# ArduOSD_Simple.net
KiCad netlist of a schematic drawn in EAGLE
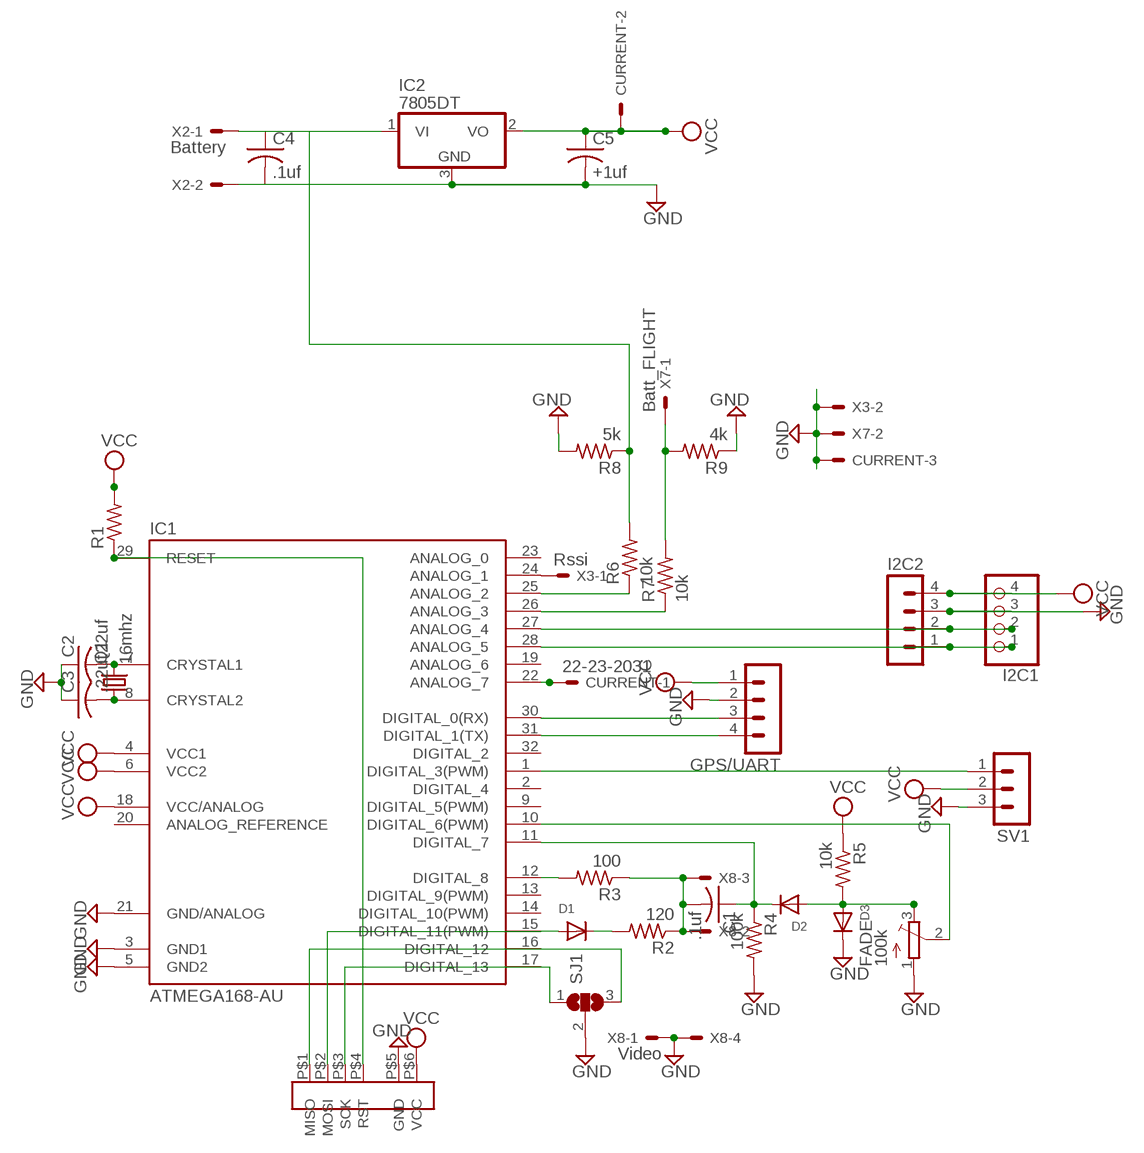
[diagram p0: schematic, sheet 1]

(export (version "E")
  (design (tool "Eeschema 10.0.6"))
  (components
    (comp (ref "C1")
      (value ".1uf")
      (footprint "eagle-import:C0805K")
      (libsource (lib "eagle-import") (part "C-USC0805K"))
    )
    (comp (ref "C2")
      (value ".22uf")
      (footprint "eagle-import:C0805K")
      (libsource (lib "eagle-import") (part "C-USC0805K"))
    )
    (comp (ref "C3")
      (value ".22uf")
      (footprint "eagle-import:C0805K")
      (libsource (lib "eagle-import") (part "C-USC0805K"))
    )
    (comp (ref "C4")
      (value ".1uf")
      (footprint "eagle-import:C0805K")
      (libsource (lib "eagle-import") (part "C-USC0805K"))
    )
    (comp (ref "C5")
      (value "+1uf")
      (footprint "eagle-import:C0805K")
      (libsource (lib "eagle-import") (part "C-USC0805K"))
    )
    (comp (ref "CURRENT")
      (value "22-23-2031")
      (footprint "eagle-import:22-23-2031")
      (fields (field (name "MF") "MOLEX"))
      (libsource (lib "eagle-import") (part "22-23-2031"))
    )
    (comp (ref "D1")
      (value "DIODESOT23_WAVE")
      (footprint "eagle-import:SOT23-W")
      (libsource (lib "eagle-import") (part "DIODESOT23_WAVE"))
    )
    (comp (ref "D2")
      (value "DIODESOT23_WAVE")
      (footprint "eagle-import:SOT23-W")
      (libsource (lib "eagle-import") (part "DIODESOT23_WAVE"))
    )
    (comp (ref "D3")
      (value "DIODESOT23_WAVE")
      (footprint "eagle-import:SOT23-W")
      (libsource (lib "eagle-import") (part "DIODESOT23_WAVE"))
    )
    (comp (ref "FADE")
      (value "100k")
      (footprint "eagle-import:TC33X")
      (libsource (lib "eagle-import") (part "TRIMPOTTC33X"))
    )
    (comp (ref "GPS/UART")
      (value "MA04-1")
      (footprint "eagle-import:MA04-1")
      (libsource (lib "eagle-import") (part "MA04-1"))
    )
    (comp (ref "I2C1")
      (value "PINHD-1X4")
      (footprint "eagle-import:1X04")
      (libsource (lib "eagle-import") (part "PINHD-1X4"))
    )
    (comp (ref "I2C2")
      (value "MA04-1")
      (footprint "eagle-import:MA04-1")
      (libsource (lib "eagle-import") (part "MA04-1"))
    )
    (comp (ref "IC1")
      (value "ATMEGA168-AU")
      (footprint "eagle-import:TQFP32-08")
      (libsource (lib "eagle-import") (part "ATMEGA168-AU"))
    )
    (comp (ref "IC2")
      (value "7805DT")
      (footprint "eagle-import:TO252")
      (libsource (lib "eagle-import") (part "78DT05"))
    )
    (comp (ref "Q1")
      (value "16mhz")
      (footprint "eagle-import:CSM-7X-DU")
      (libsource (lib "eagle-import") (part "CSM-7X-DU"))
    )
    (comp (ref "R1")
      (value "R-US_R0805")
      (footprint "eagle-import:R0805")
      (libsource (lib "eagle-import") (part "R-US_R0805"))
    )
    (comp (ref "R2")
      (value "120")
      (footprint "eagle-import:R0805")
      (libsource (lib "eagle-import") (part "R-US_R0805"))
    )
    (comp (ref "R3")
      (value "100")
      (footprint "eagle-import:R0805")
      (libsource (lib "eagle-import") (part "R-US_R0805"))
    )
    (comp (ref "R4")
      (value "100k")
      (footprint "eagle-import:R0805")
      (libsource (lib "eagle-import") (part "R-US_R0805"))
    )
    (comp (ref "R5")
      (value "10k")
      (footprint "eagle-import:R0805")
      (libsource (lib "eagle-import") (part "R-US_R0805"))
    )
    (comp (ref "R6")
      (value "10k")
      (footprint "eagle-import:R0805")
      (libsource (lib "eagle-import") (part "R-US_R0805"))
    )
    (comp (ref "R7")
      (value "10k")
      (footprint "eagle-import:R0805")
      (libsource (lib "eagle-import") (part "R-US_R0805"))
    )
    (comp (ref "R8")
      (value "5k")
      (footprint "eagle-import:R0805")
      (libsource (lib "eagle-import") (part "R-US_R0805"))
    )
    (comp (ref "R9")
      (value "4k")
      (footprint "eagle-import:R0805")
      (libsource (lib "eagle-import") (part "R-US_R0805"))
    )
    (comp (ref "SJ1")
      (value "SJ2W")
      (footprint "eagle-import:SJ_2")
      (libsource (lib "eagle-import") (part "SJ2W"))
    )
    (comp (ref "SV1")
      (value "MA03-1")
      (footprint "eagle-import:MA03-1")
      (libsource (lib "eagle-import") (part "MA03-1"))
    )
    (comp (ref "U$1")
      (value "LIN_ISP")
      (footprint "eagle-import:LINEAR_ISP")
      (libsource (lib "eagle-import") (part "LIN_ISP"))
    )
    (comp (ref "X2")
      (value "Battery")
      (footprint "eagle-import:22-23-2021")
      (fields (field (name "MF") "MOLEX") (field (name "MPN") "22-23-2021"))
      (libsource (lib "eagle-import") (part "22-23-2021"))
    )
    (comp (ref "X3")
      (value "Rssi")
      (footprint "eagle-import:22-23-2021")
      (fields (field (name "MF") "MOLEX") (field (name "MPN") "22-23-2021"))
      (libsource (lib "eagle-import") (part "22-23-2021"))
    )
    (comp (ref "X7")
      (value "Batt_FLIGHT")
      (footprint "eagle-import:22-23-2021")
      (fields (field (name "MF") "MOLEX") (field (name "MPN") "22-23-2021"))
      (libsource (lib "eagle-import") (part "22-23-2021"))
    )
    (comp (ref "X8")
      (value "Video")
      (footprint "eagle-import:22-23-2041")
      (fields (field (name "MF") "MOLEX") (field (name "MPN") "22-23-2041"))
      (libsource (lib "eagle-import") (part "22-23-2041"))
    )
  )
  (nets
    (net (code "1") (name "GND") (class "Default")
      (node (ref "C2") (pin "1") (pinfunction "1_1") (pintype "passive"))
      (node (ref "C3") (pin "1") (pinfunction "1_1") (pintype "passive"))
      (node (ref "C4") (pin "2") (pinfunction "2_2") (pintype "passive"))
      (node (ref "C5") (pin "2") (pinfunction "2_2") (pintype "passive"))
      (node (ref "CURRENT") (pin "3") (pinfunction "S_3") (pintype "passive"))
      (node (ref "D3") (pin "3") (pinfunction "C_3") (pintype "passive"))
      (node (ref "FADE") (pin "1") (pinfunction "A_1") (pintype "passive"))
      (node (ref "GPS/UART") (pin "2") (pinfunction "2_2") (pintype "passive"))
      (node (ref "I2C1") (pin "3") (pinfunction "3_3") (pintype "passive"))
      (node (ref "I2C2") (pin "3") (pinfunction "3_3") (pintype "passive"))
      (node (ref "IC1") (pin "21") (pinfunction "GND/ANALOG_21") (pintype "power_in"))
      (node (ref "IC1") (pin "3") (pinfunction "GND1_3") (pintype "power_in"))
      (node (ref "IC1") (pin "5") (pinfunction "GND2_5") (pintype "power_in"))
      (node (ref "IC2") (pin "3") (pinfunction "GND_3") (pintype "passive"))
      (node (ref "R4") (pin "2") (pinfunction "2_2") (pintype "passive"))
      (node (ref "R8") (pin "2") (pinfunction "2_2") (pintype "passive"))
      (node (ref "R9") (pin "1") (pinfunction "1_1") (pintype "passive"))
      (node (ref "SJ1") (pin "2") (pinfunction "2_2") (pintype "passive"))
      (node (ref "SV1") (pin "3") (pinfunction "3_3") (pintype "passive"))
      (node (ref "U$1") (pin "P$5") (pinfunction "GND_P$5") (pintype "bidirectional"))
      (node (ref "X2") (pin "2") (pinfunction "S_2") (pintype "passive"))
      (node (ref "X3") (pin "2") (pinfunction "S_2") (pintype "passive"))
      (node (ref "X7") (pin "2") (pinfunction "S_2") (pintype "passive"))
      (node (ref "X8") (pin "1") (pinfunction "S_1") (pintype "passive"))
      (node (ref "X8") (pin "4") (pinfunction "S_4") (pintype "passive"))
    )
    (net (code "2") (name "Net-(CURRENTA-S)") (class "Default")
      (node (ref "CURRENT") (pin "1") (pinfunction "S_1") (pintype "passive"))
      (node (ref "IC1") (pin "22") (pinfunction "ANALOG_7_22") (pintype "passive"))
    )
    (net (code "3") (name "Net-(D1-A)") (class "Default")
      (node (ref "D1") (pin "1") (pinfunction "A_1") (pintype "passive"))
      (node (ref "IC1") (pin "15") (pinfunction "DIGITAL_11(PWM)_15") (pintype "bidirectional"))
      (node (ref "U$1") (pin "P$2") (pinfunction "MOSI_P$2") (pintype "bidirectional"))
    )
    (net (code "4") (name "Net-(D1-C)") (class "Default")
      (node (ref "D1") (pin "3") (pinfunction "C_3") (pintype "passive"))
      (node (ref "R2") (pin "2") (pinfunction "2_2") (pintype "passive"))
    )
    (net (code "5") (name "Net-(D2-A)") (class "Default")
      (node (ref "D2") (pin "1") (pinfunction "A_1") (pintype "passive"))
      (node (ref "D3") (pin "1") (pinfunction "A_1") (pintype "passive"))
      (node (ref "FADE") (pin "3") (pinfunction "E_3") (pintype "passive"))
      (node (ref "R5") (pin "2") (pinfunction "2_2") (pintype "passive"))
    )
    (net (code "6") (name "Net-(D2-C)") (class "Default")
      (node (ref "C1") (pin "1") (pinfunction "1_1") (pintype "passive"))
      (node (ref "D2") (pin "3") (pinfunction "C_3") (pintype "passive"))
      (node (ref "IC1") (pin "11") (pinfunction "DIGITAL_7_11") (pintype "bidirectional"))
      (node (ref "R4") (pin "1") (pinfunction "1_1") (pintype "passive"))
    )
    (net (code "7") (name "Net-(FADE-S)") (class "Default")
      (node (ref "FADE") (pin "2") (pinfunction "S_2") (pintype "passive"))
      (node (ref "IC1") (pin "10") (pinfunction "DIGITAL_6(PWM)_10") (pintype "bidirectional"))
    )
    (net (code "8") (name "Net-(IC1-ANALOG_1)") (class "Default")
      (node (ref "IC1") (pin "24") (pinfunction "ANALOG_1_24") (pintype "bidirectional"))
      (node (ref "X3") (pin "1") (pinfunction "S_1") (pintype "passive"))
    )
    (net (code "9") (name "Net-(IC1-ANALOG_2)") (class "Default")
      (node (ref "IC1") (pin "25") (pinfunction "ANALOG_2_25") (pintype "bidirectional"))
      (node (ref "R6") (pin "1") (pinfunction "1_1") (pintype "passive"))
    )
    (net (code "10") (name "Net-(IC1-ANALOG_3)") (class "Default")
      (node (ref "IC1") (pin "26") (pinfunction "ANALOG_3_26") (pintype "bidirectional"))
      (node (ref "R7") (pin "1") (pinfunction "1_1") (pintype "passive"))
    )
    (net (code "11") (name "Net-(IC1-ANALOG_4)") (class "Default")
      (node (ref "I2C1") (pin "2") (pinfunction "2_2") (pintype "passive"))
      (node (ref "I2C2") (pin "2") (pinfunction "2_2") (pintype "passive"))
      (node (ref "IC1") (pin "27") (pinfunction "ANALOG_4_27") (pintype "bidirectional"))
    )
    (net (code "12") (name "Net-(IC1-ANALOG_5)") (class "Default")
      (node (ref "I2C1") (pin "1") (pinfunction "1_1") (pintype "passive"))
      (node (ref "I2C2") (pin "1") (pinfunction "1_1") (pintype "passive"))
      (node (ref "IC1") (pin "28") (pinfunction "ANALOG_5_28") (pintype "bidirectional"))
    )
    (net (code "13") (name "Net-(IC1-CRYSTAL1)") (class "Default")
      (node (ref "C2") (pin "2") (pinfunction "2_2") (pintype "passive"))
      (node (ref "IC1") (pin "7") (pinfunction "CRYSTAL1_7") (pintype "bidirectional"))
      (node (ref "Q1") (pin "2") (pinfunction "2_2") (pintype "passive"))
    )
    (net (code "14") (name "Net-(IC1-CRYSTAL2)") (class "Default")
      (node (ref "C3") (pin "2") (pinfunction "2_2") (pintype "passive"))
      (node (ref "IC1") (pin "8") (pinfunction "CRYSTAL2_8") (pintype "bidirectional"))
      (node (ref "Q1") (pin "1") (pinfunction "1_1") (pintype "passive"))
    )
    (net (code "15") (name "Net-(IC1-DIGITAL_0(RX))") (class "Default")
      (node (ref "GPS/UART") (pin "3") (pinfunction "3_3") (pintype "passive"))
      (node (ref "IC1") (pin "30") (pinfunction "DIGITAL_0(RX)_30") (pintype "bidirectional"))
    )
    (net (code "16") (name "Net-(IC1-DIGITAL_1(TX))") (class "Default")
      (node (ref "GPS/UART") (pin "4") (pinfunction "4_4") (pintype "passive"))
      (node (ref "IC1") (pin "31") (pinfunction "DIGITAL_1(TX)_31") (pintype "bidirectional"))
    )
    (net (code "17") (name "Net-(IC1-DIGITAL_3(PWM))") (class "Default")
      (node (ref "IC1") (pin "1") (pinfunction "DIGITAL_3(PWM)_1") (pintype "bidirectional"))
      (node (ref "SV1") (pin "1") (pinfunction "1_1") (pintype "passive"))
    )
    (net (code "18") (name "Net-(IC1-DIGITAL_8)") (class "Default")
      (node (ref "IC1") (pin "12") (pinfunction "DIGITAL_8_12") (pintype "bidirectional"))
      (node (ref "R3") (pin "2") (pinfunction "2_2") (pintype "passive"))
    )
    (net (code "19") (name "Net-(IC1-DIGITAL_12)") (class "Default")
      (node (ref "IC1") (pin "16") (pinfunction "DIGITAL_12_16") (pintype "bidirectional"))
      (node (ref "SJ1") (pin "3") (pinfunction "3_3") (pintype "passive"))
      (node (ref "U$1") (pin "P$1") (pinfunction "MISO_P$1") (pintype "bidirectional"))
    )
    (net (code "20") (name "Net-(IC1-DIGITAL_13)") (class "Default")
      (node (ref "IC1") (pin "17") (pinfunction "DIGITAL_13_17") (pintype "bidirectional"))
      (node (ref "SJ1") (pin "1") (pinfunction "1_1") (pintype "passive"))
      (node (ref "U$1") (pin "P$3") (pinfunction "SCK_P$3") (pintype "bidirectional"))
    )
    (net (code "21") (name "Net-(IC1-RESET)") (class "Default")
      (node (ref "IC1") (pin "29") (pinfunction "RESET_29") (pintype "bidirectional"))
      (node (ref "R1") (pin "1") (pinfunction "1_1") (pintype "passive"))
      (node (ref "U$1") (pin "P$4") (pinfunction "RST_P$4") (pintype "bidirectional"))
    )
    (net (code "22") (name "Net-(IC2-VI)") (class "Default")
      (node (ref "C4") (pin "1") (pinfunction "1_1") (pintype "passive"))
      (node (ref "IC2") (pin "1") (pinfunction "VI_1") (pintype "input"))
      (node (ref "R6") (pin "2") (pinfunction "2_2") (pintype "passive"))
      (node (ref "R8") (pin "1") (pinfunction "1_1") (pintype "passive"))
      (node (ref "X2") (pin "1") (pinfunction "S_1") (pintype "passive"))
    )
    (net (code "23") (name "Net-(X7A-S)") (class "Default")
      (node (ref "R7") (pin "2") (pinfunction "2_2") (pintype "passive"))
      (node (ref "R9") (pin "2") (pinfunction "2_2") (pintype "passive"))
      (node (ref "X7") (pin "1") (pinfunction "S_1") (pintype "passive"))
    )
    (net (code "24") (name "Net-(X8B-S)") (class "Default")
      (node (ref "C1") (pin "2") (pinfunction "2_2") (pintype "passive"))
      (node (ref "R2") (pin "1") (pinfunction "1_1") (pintype "passive"))
      (node (ref "R3") (pin "1") (pinfunction "1_1") (pintype "passive"))
      (node (ref "X8") (pin "2") (pinfunction "S_2") (pintype "passive"))
      (node (ref "X8") (pin "3") (pinfunction "S_3") (pintype "passive"))
    )
    (net (code "25") (name "VCC") (class "Default")
      (node (ref "C5") (pin "1") (pinfunction "1_1") (pintype "passive"))
      (node (ref "CURRENT") (pin "2") (pinfunction "S_2") (pintype "passive"))
      (node (ref "GPS/UART") (pin "1") (pinfunction "1_1") (pintype "passive"))
      (node (ref "I2C1") (pin "4") (pinfunction "4_4") (pintype "passive"))
      (node (ref "I2C2") (pin "4") (pinfunction "4_4") (pintype "passive"))
      (node (ref "IC1") (pin "18") (pinfunction "VCC/ANALOG_18") (pintype "passive"))
      (node (ref "IC1") (pin "4") (pinfunction "VCC1_4") (pintype "power_in"))
      (node (ref "IC1") (pin "6") (pinfunction "VCC2_6") (pintype "power_in"))
      (node (ref "IC2") (pin "2") (pinfunction "VO_2") (pintype "passive"))
      (node (ref "R1") (pin "2") (pinfunction "2_2") (pintype "passive"))
      (node (ref "R5") (pin "1") (pinfunction "1_1") (pintype "passive"))
      (node (ref "SV1") (pin "2") (pinfunction "2_2") (pintype "passive"))
      (node (ref "U$1") (pin "P$6") (pinfunction "VCC_P$6") (pintype "bidirectional"))
    )
    (net (code "26") (name "unconnected-(IC1-ANALOG_0-Pad23)") (class "Default")
      (node (ref "IC1") (pin "23") (pinfunction "ANALOG_0_23") (pintype "bidirectional"))
    )
    (net (code "27") (name "unconnected-(IC1-ANALOG_6-Pad19)") (class "Default")
      (node (ref "IC1") (pin "19") (pinfunction "ANALOG_6_19") (pintype "passive"))
    )
    (net (code "28") (name "unconnected-(IC1-ANALOG_REFERENCE-Pad20)") (class "Default")
      (node (ref "IC1") (pin "20") (pinfunction "ANALOG_REFERENCE_20") (pintype "passive"))
    )
    (net (code "29") (name "unconnected-(IC1-DIGITAL_2-Pad32)") (class "Default")
      (node (ref "IC1") (pin "32") (pinfunction "DIGITAL_2_32") (pintype "bidirectional"))
    )
    (net (code "30") (name "unconnected-(IC1-DIGITAL_4-Pad2)") (class "Default")
      (node (ref "IC1") (pin "2") (pinfunction "DIGITAL_4_2") (pintype "bidirectional"))
    )
    (net (code "31") (name "unconnected-(IC1-DIGITAL_5(PWM)-Pad9)") (class "Default")
      (node (ref "IC1") (pin "9") (pinfunction "DIGITAL_5(PWM)_9") (pintype "bidirectional"))
    )
    (net (code "32") (name "unconnected-(IC1-DIGITAL_9(PWM)-Pad13)") (class "Default")
      (node (ref "IC1") (pin "13") (pinfunction "DIGITAL_9(PWM)_13") (pintype "bidirectional"))
    )
    (net (code "33") (name "unconnected-(IC1-DIGITAL_10(PWM)-Pad14)") (class "Default")
      (node (ref "IC1") (pin "14") (pinfunction "DIGITAL_10(PWM)_14") (pintype "bidirectional"))
    )
  )
)
